# esp_thermometer.net
KiCad netlist of a schematic drawn in EAGLE
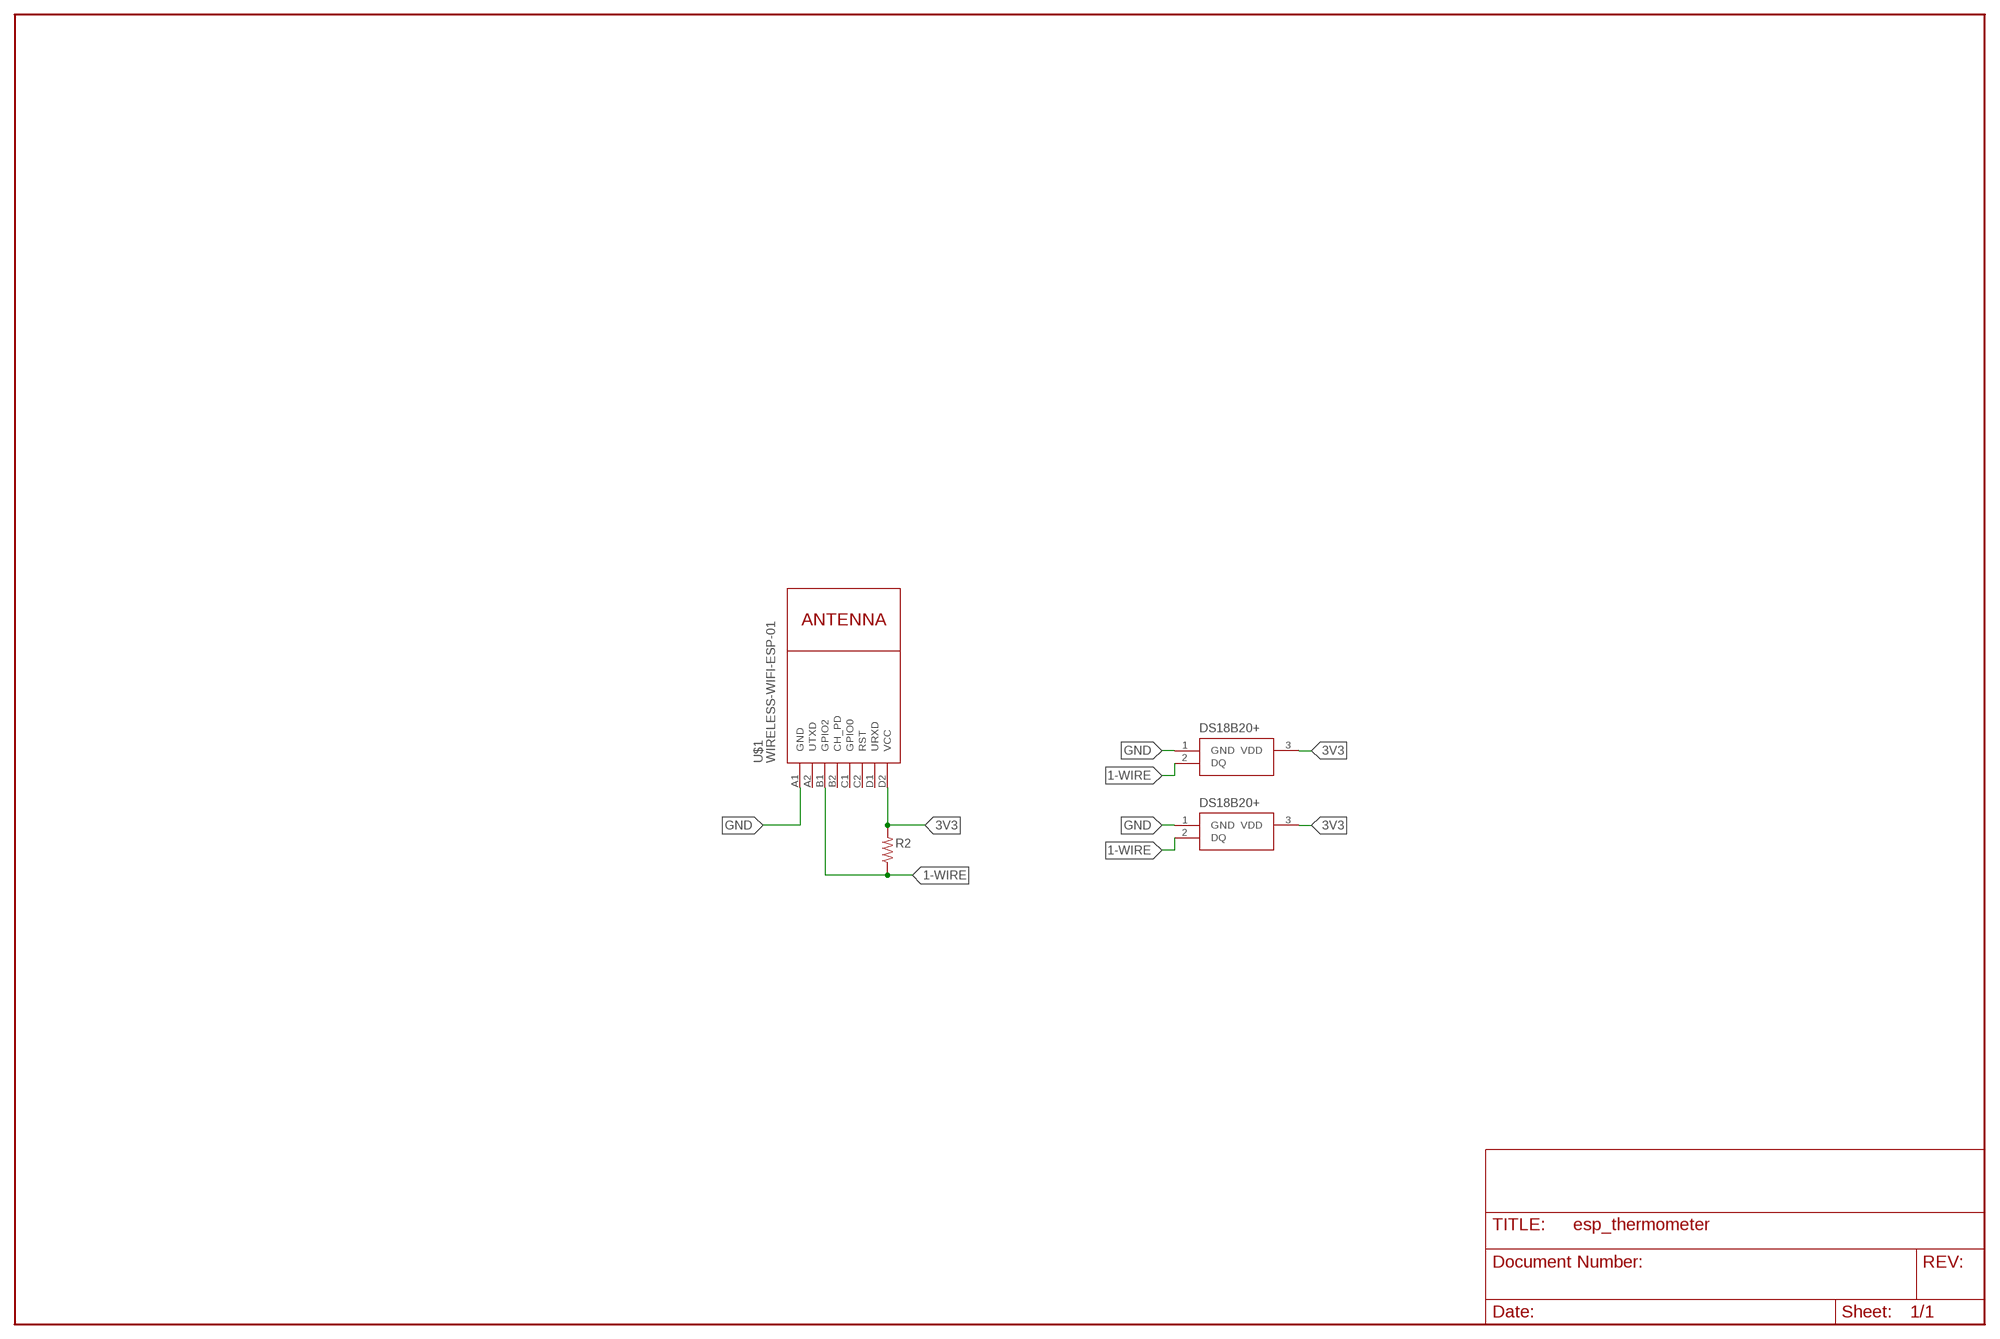
[diagram p0: schematic, sheet 1]

(export (version "E")
  (design (tool "Eeschema 10.0.6"))
  (components
    (comp (ref "IC2")
      (value "DS18B20+")
      (footprint "eagle-import:TO-92")
      (fields (field (name "MOUSER_PART_NUMBER") "700-DS18B20+"))
      (libsource (lib "eagle-import") (part "DS18B20+"))
    )
    (comp (ref "IC3")
      (value "DS18B20+")
      (footprint "eagle-import:TO-92")
      (fields (field (name "MOUSER_PART_NUMBER") "700-DS18B20+"))
      (libsource (lib "eagle-import") (part "DS18B20+"))
    )
    (comp (ref "R2")
      (value "R-US_0204/7")
      (footprint "eagle-import:0204_7")
      (libsource (lib "eagle-import") (part "R-US_0204/7"))
    )
    (comp (ref "U$1")
      (value "WIRELESS-WIFI-ESP-01")
      (footprint "eagle-import:WIRELESS-WIFI-ESP-01")
      (libsource (lib "eagle-import") (part "WIRELESS-WIFI-ESP-01"))
    )
  )
  (nets
    (net (code "1") (name "1-WIRE") (class "Default")
      (node (ref "IC2") (pin "2") (pinfunction "DQ_2") (pintype "bidirectional"))
      (node (ref "IC3") (pin "2") (pinfunction "DQ_2") (pintype "bidirectional"))
    )
    (net (code "2") (name "3V3") (class "Default")
      (node (ref "IC2") (pin "3") (pinfunction "VDD_3") (pintype "power_in"))
    )
    (net (code "3") (name "GND") (class "Default")
      (node (ref "IC2") (pin "1") (pinfunction "GND_1") (pintype "power_in"))
      (node (ref "IC3") (pin "1") (pinfunction "GND_1") (pintype "power_in"))
    )
    (net (code "4") (name "Net-(U$1-GPIO2)") (class "Default")
      (node (ref "R2") (pin "1") (pinfunction "1_1") (pintype "passive"))
      (node (ref "U$1") (pin "B1") (pinfunction "GPIO2_B1") (pintype "bidirectional"))
    )
    (net (code "5") (name "Net-(U$1-VCC)") (class "Default")
      (node (ref "R2") (pin "2") (pinfunction "2_2") (pintype "passive"))
      (node (ref "U$1") (pin "D2") (pinfunction "VCC_D2") (pintype "power_in"))
    )
    (net (code "6") (name "unconnected-(IC3-VDD-Pad3)") (class "Default")
      (node (ref "IC3") (pin "3") (pinfunction "VDD_3") (pintype "power_in"))
    )
    (net (code "7") (name "unconnected-(U$1-CH_PD-PadB2)") (class "Default")
      (node (ref "U$1") (pin "B2") (pinfunction "CH_PD_B2") (pintype "bidirectional"))
    )
    (net (code "8") (name "unconnected-(U$1-GND-PadA1)") (class "Default")
      (node (ref "U$1") (pin "A1") (pinfunction "GND_A1") (pintype "power_in"))
    )
    (net (code "9") (name "unconnected-(U$1-GPIO0-PadC1)") (class "Default")
      (node (ref "U$1") (pin "C1") (pinfunction "GPIO0_C1") (pintype "bidirectional"))
    )
    (net (code "10") (name "unconnected-(U$1-RST-PadC2)") (class "Default")
      (node (ref "U$1") (pin "C2") (pinfunction "RST_C2") (pintype "bidirectional"))
    )
    (net (code "11") (name "unconnected-(U$1-URXD-PadD1)") (class "Default")
      (node (ref "U$1") (pin "D1") (pinfunction "URXD_D1") (pintype "bidirectional"))
    )
    (net (code "12") (name "unconnected-(U$1-UTXD-PadA2)") (class "Default")
      (node (ref "U$1") (pin "A2") (pinfunction "UTXD_A2") (pintype "bidirectional"))
    )
  )
)
